# 13A-001.net
KiCad netlist of a schematic drawn in EAGLE
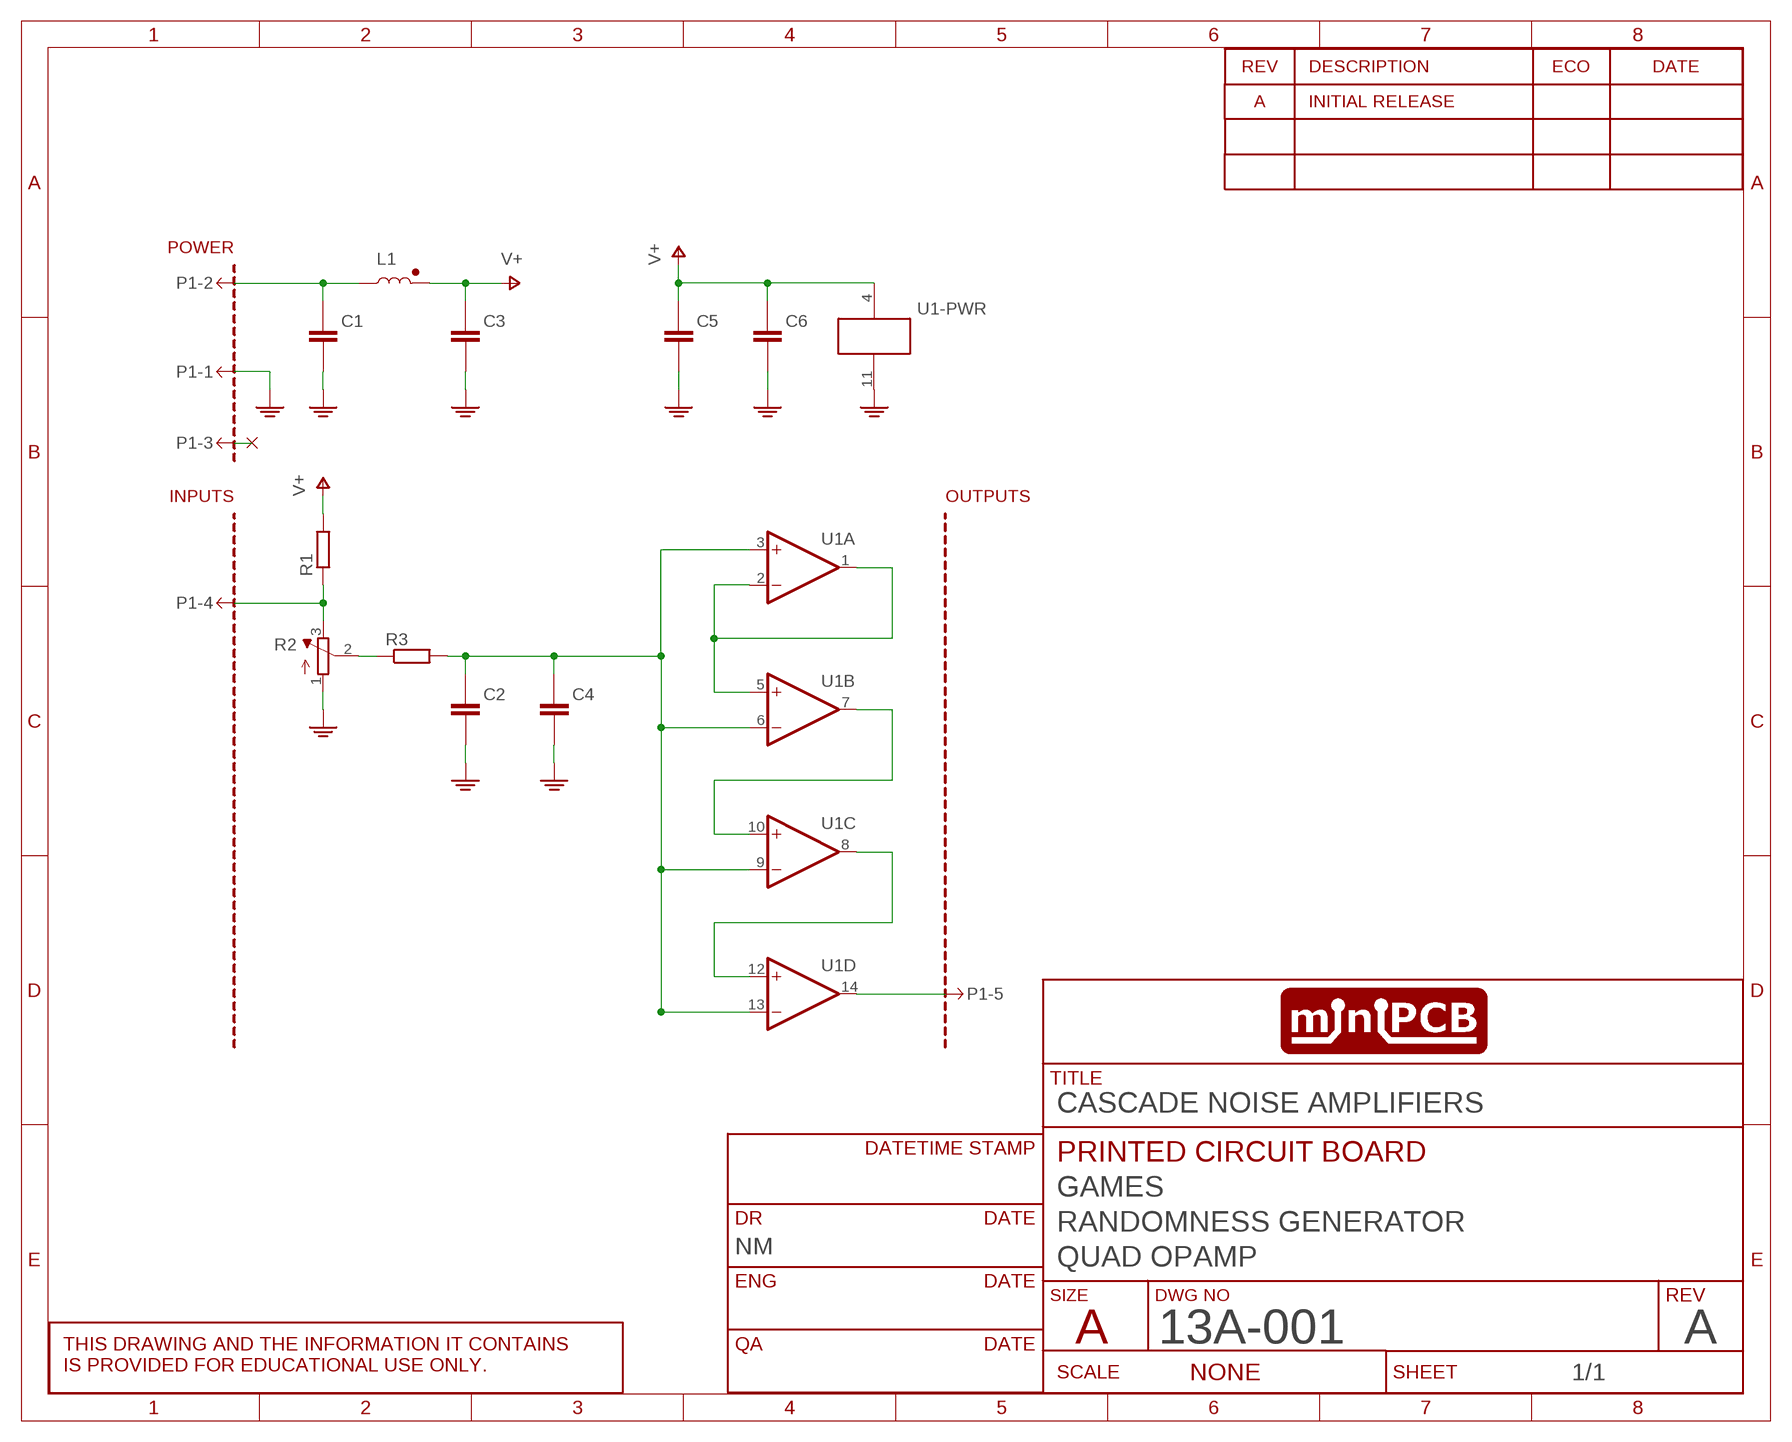
[diagram p0: schematic, sheet 1]

(export (version "E")
  (design (tool "Eeschema 10.0.6"))
  (components
    (comp (ref "C1")
      (value "CAPACITOR_10")
      (footprint "eagle-import:C5MM")
      (libsource (lib "eagle-import") (part "CAPACITOR_10"))
    )
    (comp (ref "C2")
      (value "CAPACITORTHD")
      (footprint "eagle-import:C050-024X044")
      (libsource (lib "eagle-import") (part "CAPACITORTHD"))
    )
    (comp (ref "C3")
      (value "CAPACITOR_10")
      (footprint "eagle-import:C5MM")
      (libsource (lib "eagle-import") (part "CAPACITOR_10"))
    )
    (comp (ref "C4")
      (value "CAPACITORTHD")
      (footprint "eagle-import:C050-024X044")
      (libsource (lib "eagle-import") (part "CAPACITORTHD"))
    )
    (comp (ref "C5")
      (value "CAPACITORTHD")
      (footprint "eagle-import:C050-024X044")
      (libsource (lib "eagle-import") (part "CAPACITORTHD"))
    )
    (comp (ref "C6")
      (value "CAPACITORTHD")
      (footprint "eagle-import:C050-024X044")
      (libsource (lib "eagle-import") (part "CAPACITORTHD"))
    )
    (comp (ref "L1")
      (value "INDUCTORRFS1113")
      (footprint "eagle-import:L_RFS1113")
      (libsource (lib "eagle-import") (part "INDUCTORRFS1113"))
    )
    (comp (ref "P1-")
      (value "MINIPCB_5P50X50")
      (footprint "eagle-import:MINIPCB_5P_50X50MM")
      (libsource (lib "eagle-import") (part "MINIPCB_5P50X50"))
    )
    (comp (ref "R1")
      (value "RESISTORTHD")
      (footprint "eagle-import:0204_10")
      (libsource (lib "eagle-import") (part "RESISTORTHD"))
    )
    (comp (ref "R2")
      (value "TRIMPOT0.100THD")
      (footprint "eagle-import:TRIM_0100")
      (libsource (lib "eagle-import") (part "TRIMPOT0.100THD"))
    )
    (comp (ref "R3")
      (value "RESISTORTHD")
      (footprint "eagle-import:0204_10")
      (libsource (lib "eagle-import") (part "RESISTORTHD"))
    )
    (comp (ref "U1")
      (value "OPAMP_QUADTHD")
      (footprint "eagle-import:DIL14")
      (libsource (lib "eagle-import") (part "OPAMP_QUADTHD"))
    )
  )
  (nets
    (net (code "1") (name "GND") (class "Default")
      (node (ref "C1") (pin "-") (pinfunction "-_-") (pintype "passive"))
      (node (ref "C2") (pin "2") (pinfunction "-_2") (pintype "passive"))
      (node (ref "C3") (pin "-") (pinfunction "-_-") (pintype "passive"))
      (node (ref "C4") (pin "2") (pinfunction "-_2") (pintype "passive"))
      (node (ref "C5") (pin "2") (pinfunction "-_2") (pintype "passive"))
      (node (ref "C6") (pin "2") (pinfunction "-_2") (pintype "passive"))
      (node (ref "P1-") (pin "1") (pinfunction "1_1") (pintype "bidirectional"))
      (node (ref "R2") (pin "1") (pinfunction "A_1") (pintype "passive"))
      (node (ref "U1") (pin "11") (pinfunction "V-_11") (pintype "power_in"))
    )
    (net (code "2") (name "Net-(C2-+)") (class "Default")
      (node (ref "C2") (pin "1") (pinfunction "+_1") (pintype "passive"))
      (node (ref "C4") (pin "1") (pinfunction "+_1") (pintype "passive"))
      (node (ref "R3") (pin "2") (pinfunction "2_2") (pintype "passive"))
      (node (ref "U1") (pin "13") (pinfunction "-IN_13") (pintype "input"))
      (node (ref "U1") (pin "3") (pinfunction "+IN_3") (pintype "input"))
      (node (ref "U1") (pin "6") (pinfunction "-IN_6") (pintype "input"))
      (node (ref "U1") (pin "9") (pinfunction "-IN_9") (pintype "input"))
    )
    (net (code "3") (name "Net-(P1-B-1)") (class "Default")
      (node (ref "C1") (pin "+") (pinfunction "+_+") (pintype "passive"))
      (node (ref "L1") (pin "2") (pinfunction "2_2") (pintype "passive"))
      (node (ref "P1-") (pin "2") (pinfunction "1_2") (pintype "bidirectional"))
    )
    (net (code "4") (name "Net-(P1-D-1)") (class "Default")
      (node (ref "P1-") (pin "4") (pinfunction "1_4") (pintype "bidirectional"))
      (node (ref "R1") (pin "1") (pinfunction "1_1") (pintype "passive"))
      (node (ref "R2") (pin "3") (pinfunction "E_3") (pintype "passive"))
    )
    (net (code "5") (name "Net-(P1-H-1)") (class "Default")
      (node (ref "P1-") (pin "5") (pinfunction "1_5") (pintype "bidirectional"))
      (node (ref "U1") (pin "14") (pinfunction "OUT_14") (pintype "output"))
    )
    (net (code "6") (name "Net-(R2-S)") (class "Default")
      (node (ref "R2") (pin "2") (pinfunction "S_2") (pintype "passive"))
      (node (ref "R3") (pin "1") (pinfunction "1_1") (pintype "passive"))
    )
    (net (code "7") (name "Net-(U1B--IN)") (class "Default")
      (node (ref "U1") (pin "1") (pinfunction "OUT_1") (pintype "output"))
      (node (ref "U1") (pin "2") (pinfunction "-IN_2") (pintype "input"))
      (node (ref "U1") (pin "5") (pinfunction "+IN_5") (pintype "input"))
    )
    (net (code "8") (name "Net-(U1C-OUT)") (class "Default")
      (node (ref "U1") (pin "10") (pinfunction "+IN_10") (pintype "input"))
      (node (ref "U1") (pin "7") (pinfunction "OUT_7") (pintype "output"))
    )
    (net (code "9") (name "Net-(U1D-OUT)") (class "Default")
      (node (ref "U1") (pin "12") (pinfunction "+IN_12") (pintype "input"))
      (node (ref "U1") (pin "8") (pinfunction "OUT_8") (pintype "output"))
    )
    (net (code "10") (name "V+") (class "Default")
      (node (ref "C3") (pin "+") (pinfunction "+_+") (pintype "passive"))
      (node (ref "C5") (pin "1") (pinfunction "+_1") (pintype "passive"))
      (node (ref "C6") (pin "1") (pinfunction "+_1") (pintype "passive"))
      (node (ref "L1") (pin "1") (pinfunction "1_1") (pintype "passive"))
      (node (ref "R1") (pin "2") (pinfunction "2_2") (pintype "passive"))
      (node (ref "U1") (pin "4") (pinfunction "V+_4") (pintype "power_in"))
    )
    (net (code "11") (name "unconnected-(P1-C-1-Pad3)") (class "Default")
      (node (ref "P1-") (pin "3") (pinfunction "1_3") (pintype "bidirectional"))
    )
  )
)
